# DC24_HHV_RE-revA.net
KiCad netlist of a schematic drawn in EAGLE
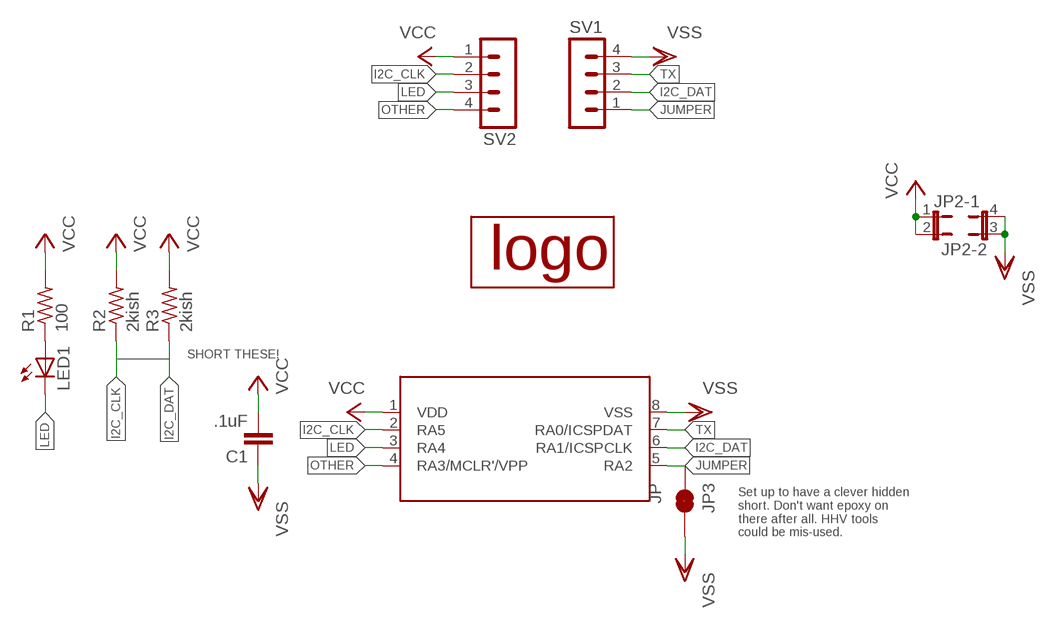
[diagram p0: schematic, sheet 1]

(export (version "E")
  (design (tool "Eeschema 10.0.6"))
  (components
    (comp (ref "C1")
      (value ".1uF")
      (footprint "eagle-import:C050-024X044")
      (libsource (lib "eagle-import") (part "C-EU050-024X044"))
    )
    (comp (ref "JP2")
      (value "JP2QE")
      (footprint "eagle-import:JP2Q")
      (libsource (lib "eagle-import") (part "JP2QE"))
    )
    (comp (ref "JP3")
      (value "JP")
      (footprint "eagle-import:PAD-JUMPER-2-NC_BY_TRACE_YES_SILK")
      (libsource (lib "eagle-import") (part "JUMPER-PAD-2-NC_BY_TRACE"))
    )
    (comp (ref "LED1")
      (value "LED5MM")
      (footprint "eagle-import:LED5MM")
      (libsource (lib "eagle-import") (part "LED5MM"))
    )
    (comp (ref "R1")
      (value "100")
      (footprint "eagle-import:0204_7")
      (libsource (lib "eagle-import") (part "R-US_0204/7"))
    )
    (comp (ref "R2")
      (value "2kish")
      (footprint "eagle-import:0204_7")
      (libsource (lib "eagle-import") (part "R-US_0204/7"))
    )
    (comp (ref "R3")
      (value "2kish")
      (footprint "eagle-import:0204_7")
      (libsource (lib "eagle-import") (part "R-US_0204/7"))
    )
    (comp (ref "SV1")
      (value "MA04-1")
      (footprint "eagle-import:MA04-1")
      (libsource (lib "eagle-import") (part "MA04-1"))
    )
    (comp (ref "SV2")
      (value "MA04-1")
      (footprint "eagle-import:MA04-1")
      (libsource (lib "eagle-import") (part "MA04-1"))
    )
    (comp (ref "U$1")
      (value "KBELOGO-SILK")
      (footprint "eagle-import:KBELOGO-SILK")
      (libsource (lib "eagle-import") (part "KBELOGO-SILK"))
    )
    (comp (ref "U1")
      (value "PIC12F1571")
      (footprint "eagle-import:DIL8")
      (libsource (lib "eagle-import") (part "PIC12F1571"))
    )
  )
  (nets
    (net (code "1") (name "I2C_CLK") (class "Default")
      (node (ref "R2") (pin "1") (pinfunction "1_1") (pintype "passive"))
      (node (ref "SV2") (pin "2") (pinfunction "2_2") (pintype "passive"))
      (node (ref "U1") (pin "2") (pinfunction "RA5_2") (pintype "bidirectional"))
    )
    (net (code "2") (name "I2C_DAT") (class "Default")
      (node (ref "R3") (pin "1") (pinfunction "1_1") (pintype "passive"))
      (node (ref "SV1") (pin "2") (pinfunction "2_2") (pintype "passive"))
      (node (ref "U1") (pin "6") (pinfunction "RA1/ICSPCLK_6") (pintype "bidirectional"))
    )
    (net (code "3") (name "JUMPER") (class "Default")
      (node (ref "JP3") (pin "1") (pinfunction "1_1") (pintype "passive"))
      (node (ref "SV1") (pin "1") (pinfunction "1_1") (pintype "passive"))
      (node (ref "U1") (pin "5") (pinfunction "RA2_5") (pintype "bidirectional"))
    )
    (net (code "4") (name "LED") (class "Default")
      (node (ref "LED1") (pin "K") (pinfunction "C_K") (pintype "passive"))
      (node (ref "SV2") (pin "3") (pinfunction "3_3") (pintype "passive"))
      (node (ref "U1") (pin "3") (pinfunction "RA4_3") (pintype "bidirectional"))
    )
    (net (code "5") (name "Net-(LED1-PadA)") (class "Default")
      (node (ref "LED1") (pin "A") (pinfunction "A_A") (pintype "passive"))
      (node (ref "R1") (pin "1") (pinfunction "1_1") (pintype "passive"))
    )
    (net (code "6") (name "OTHER") (class "Default")
      (node (ref "SV2") (pin "4") (pinfunction "4_4") (pintype "passive"))
      (node (ref "U1") (pin "4") (pinfunction "RA3/MCLR'/VPP_4") (pintype "bidirectional"))
    )
    (net (code "7") (name "TX") (class "Default")
      (node (ref "SV1") (pin "3") (pinfunction "3_3") (pintype "passive"))
      (node (ref "U1") (pin "7") (pinfunction "RA0/ICSPDAT_7") (pintype "bidirectional"))
    )
    (net (code "8") (name "VCC") (class "Default")
      (node (ref "C1") (pin "2") (pinfunction "2_2") (pintype "passive"))
      (node (ref "JP2") (pin "1") (pinfunction "1_1") (pintype "passive"))
      (node (ref "JP2") (pin "2") (pinfunction "2_2") (pintype "passive"))
      (node (ref "R1") (pin "2") (pinfunction "2_2") (pintype "passive"))
      (node (ref "R2") (pin "2") (pinfunction "2_2") (pintype "passive"))
      (node (ref "R3") (pin "2") (pinfunction "2_2") (pintype "passive"))
      (node (ref "SV2") (pin "1") (pinfunction "1_1") (pintype "passive"))
      (node (ref "U1") (pin "1") (pinfunction "VDD_1") (pintype "bidirectional"))
    )
    (net (code "9") (name "VSS") (class "Default")
      (node (ref "C1") (pin "1") (pinfunction "1_1") (pintype "passive"))
      (node (ref "JP2") (pin "3") (pinfunction "1_3") (pintype "passive"))
      (node (ref "JP2") (pin "4") (pinfunction "2_4") (pintype "passive"))
      (node (ref "JP3") (pin "2") (pinfunction "2_2") (pintype "passive"))
      (node (ref "SV1") (pin "4") (pinfunction "4_4") (pintype "passive"))
      (node (ref "U1") (pin "8") (pinfunction "VSS_8") (pintype "bidirectional"))
    )
  )
)
